# esploc.net
KiCad netlist of a schematic drawn in EAGLE
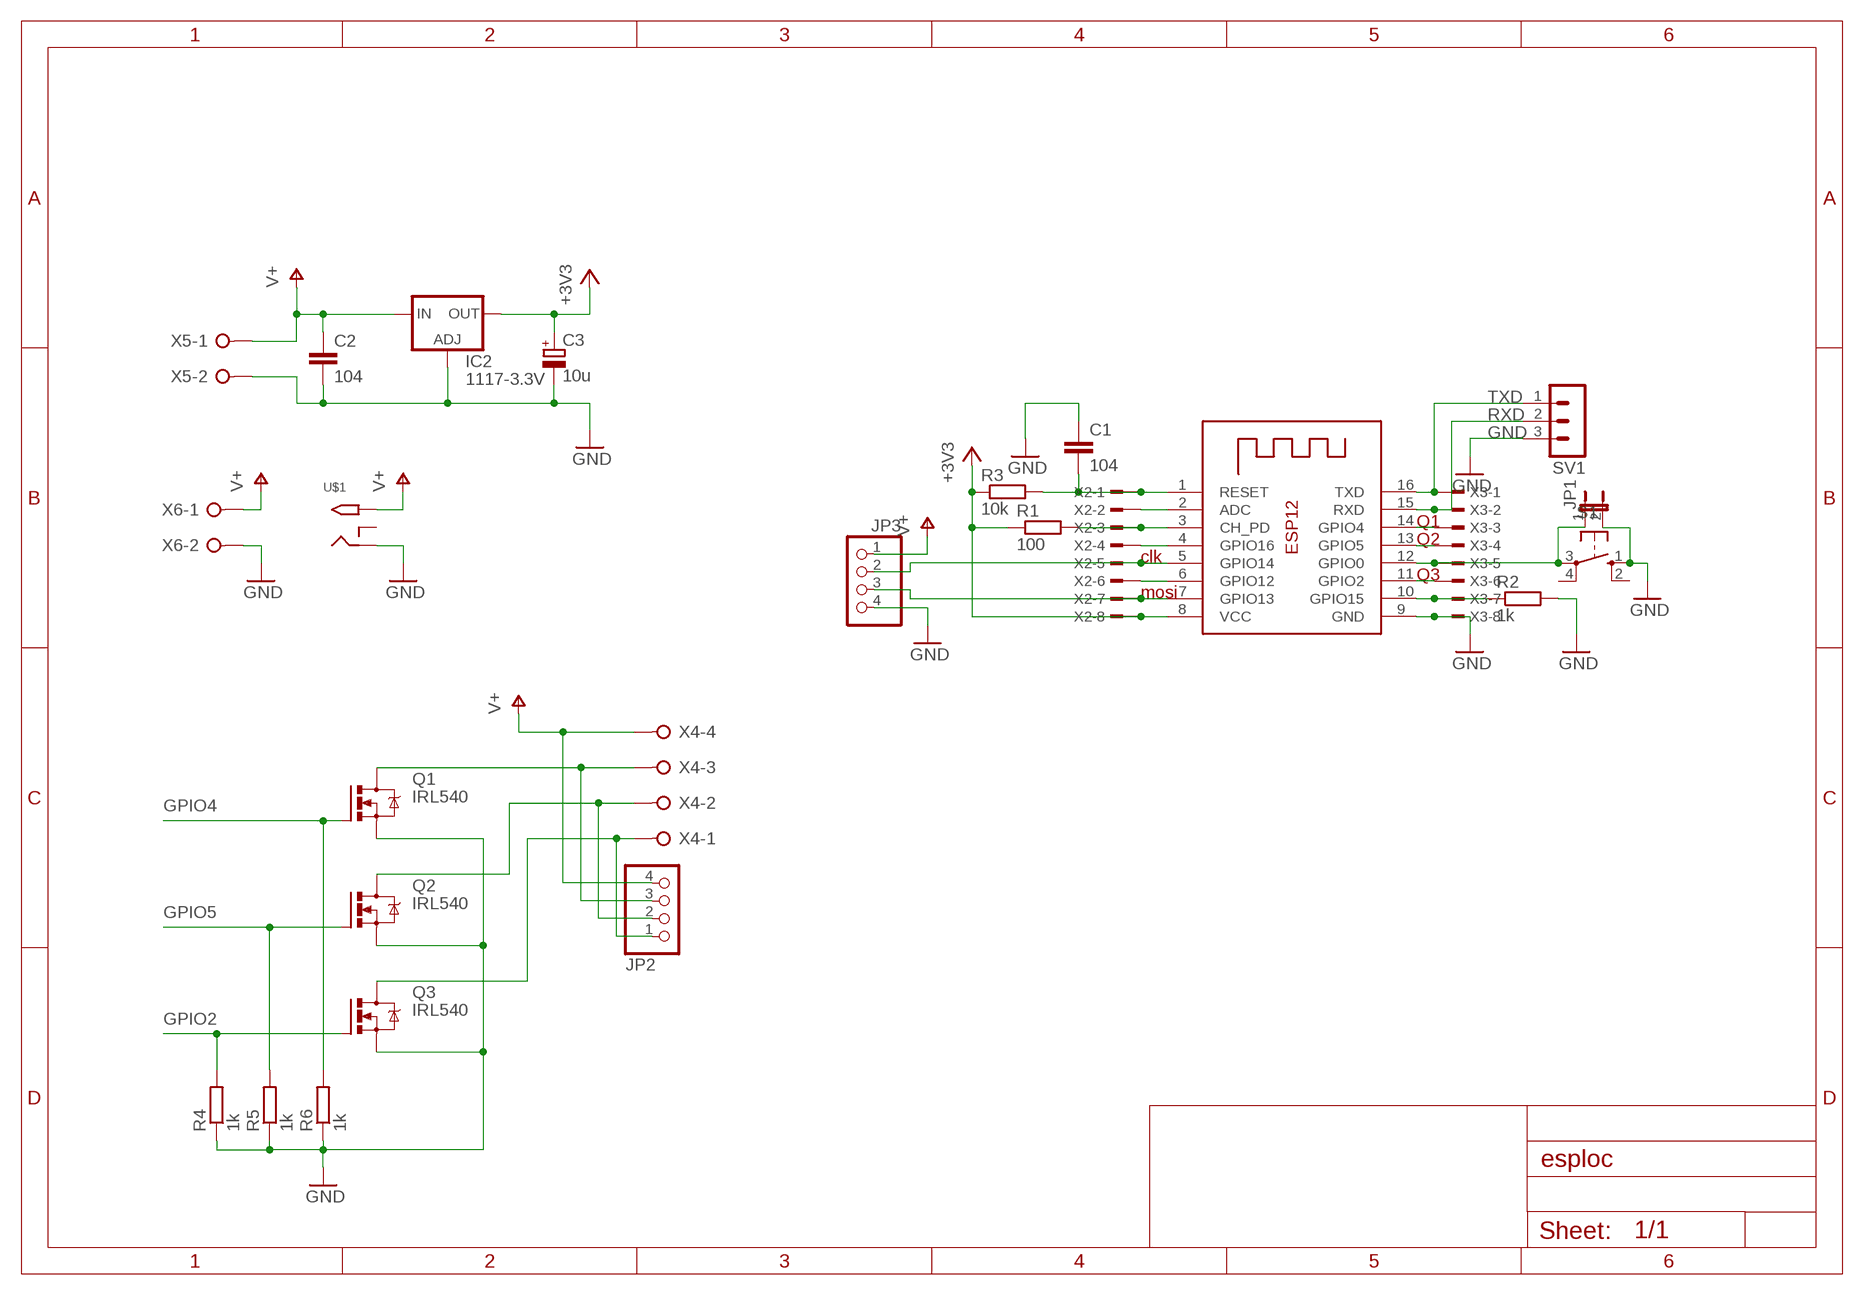
[diagram p0: schematic, sheet 1]

(export (version "E")
  (design (tool "Eeschema 10.0.6"))
  (components
    (comp (ref "C1")
      (value "104")
      (footprint "eagle-import:C025_050-025X075")
      (libsource (lib "eagle-import") (part "C-EU025_050-025X075"))
    )
    (comp (ref "C2")
      (value "104")
      (footprint "eagle-import:C025_050-025X075")
      (libsource (lib "eagle-import") (part "C-EU025_050-025X075"))
    )
    (comp (ref "C3")
      (value "10u")
      (footprint "eagle-import:E2,5-6E")
      (libsource (lib "eagle-import") (part "CPOL-EUE2,5-6E"))
    )
    (comp (ref "IC2")
      (value "1117-3.3V")
      (footprint "eagle-import:SOT223")
      (libsource (lib "eagle-import") (part "LD117A?S33TR"))
    )
    (comp (ref "JP1")
      (value "JP1E")
      (footprint "eagle-import:JP1")
      (libsource (lib "eagle-import") (part "JP1E"))
    )
    (comp (ref "JP2")
      (value "PINHD-1X4")
      (footprint "eagle-import:1X04")
      (libsource (lib "eagle-import") (part "PINHD-1X4"))
    )
    (comp (ref "JP3")
      (value "PINHD-1X4")
      (footprint "eagle-import:1X04")
      (libsource (lib "eagle-import") (part "PINHD-1X4"))
    )
    (comp (ref "Q1")
      (value "IRL540")
      (footprint "eagle-import:TO220BV")
      (libsource (lib "eagle-import") (part "IRF540"))
    )
    (comp (ref "Q2")
      (value "IRL540")
      (footprint "eagle-import:TO220BV")
      (libsource (lib "eagle-import") (part "IRF540"))
    )
    (comp (ref "Q3")
      (value "IRL540")
      (footprint "eagle-import:TO220BV")
      (libsource (lib "eagle-import") (part "IRF540"))
    )
    (comp (ref "R1")
      (value "100")
      (footprint "eagle-import:M0805")
      (libsource (lib "eagle-import") (part "R-EU_M0805"))
    )
    (comp (ref "R2")
      (value "1k")
      (footprint "eagle-import:M0805")
      (libsource (lib "eagle-import") (part "R-EU_M0805"))
    )
    (comp (ref "R3")
      (value "10k")
      (footprint "eagle-import:M0805")
      (libsource (lib "eagle-import") (part "R-EU_M0805"))
    )
    (comp (ref "R4")
      (value "1k")
      (footprint "eagle-import:M0805")
      (libsource (lib "eagle-import") (part "R-EU_M0805"))
    )
    (comp (ref "R5")
      (value "1k")
      (footprint "eagle-import:M0805")
      (libsource (lib "eagle-import") (part "R-EU_M0805"))
    )
    (comp (ref "R6")
      (value "1k")
      (footprint "eagle-import:M0805")
      (libsource (lib "eagle-import") (part "R-EU_M0805"))
    )
    (comp (ref "S1")
      (value "40-XX")
      (footprint "eagle-import:B3F-40XX")
      (fields (field (name "MF") "OMRON COMPONENTS USA") (field (name "MPN") "B3F-4000"))
      (libsource (lib "eagle-import") (part "40-XX"))
    )
    (comp (ref "SV1")
      (value "MA03-1")
      (footprint "eagle-import:MA03-1")
      (libsource (lib "eagle-import") (part "MA03-1"))
    )
    (comp (ref "U$1")
      (value "2.1MMJACKTHM")
      (footprint "eagle-import:PJ-102A")
      (libsource (lib "eagle-import") (part "2.1MMJACKTHM"))
    )
    (comp (ref "X1")
      (value "ESP-12")
      (footprint "eagle-import:ESP-12")
      (libsource (lib "eagle-import") (part "ESP-12"))
    )
    (comp (ref "X2")
      (value "TSW-108-02-S-S")
      (footprint "eagle-import:TSW-108-02-S-S")
      (libsource (lib "eagle-import") (part "TSW-108-02-S-S"))
    )
    (comp (ref "X3")
      (value "TSW-108-02-S-S")
      (footprint "eagle-import:TSW-108-02-S-S")
      (libsource (lib "eagle-import") (part "TSW-108-02-S-S"))
    )
    (comp (ref "X4")
      (value "W237-04P")
      (footprint "eagle-import:W237-4P")
      (libsource (lib "eagle-import") (part "W237-04P"))
    )
    (comp (ref "X5")
      (value "W237-02P")
      (footprint "eagle-import:W237-132")
      (libsource (lib "eagle-import") (part "W237-02P"))
    )
    (comp (ref "X6")
      (value "W237-02P")
      (footprint "eagle-import:W237-132")
      (libsource (lib "eagle-import") (part "W237-02P"))
    )
  )
  (nets
    (net (code "1") (name "+3V3") (class "Default")
      (node (ref "C3") (pin "+") (pinfunction "+_+") (pintype "passive"))
      (node (ref "IC2") (pin "2") (pinfunction "OUT_2") (pintype "passive"))
      (node (ref "IC2") (pin "4") (pinfunction "OUT_4") (pintype "passive"))
      (node (ref "R1") (pin "1") (pinfunction "1_1") (pintype "passive"))
      (node (ref "R3") (pin "1") (pinfunction "1_1") (pintype "passive"))
      (node (ref "X1") (pin "8") (pinfunction "VCC_8") (pintype "power_in"))
      (node (ref "X2") (pin "8") (pinfunction "1_8") (pintype "passive"))
    )
    (net (code "2") (name "/GPIO2") (class "Default")
      (node (ref "Q3") (pin "G") (pinfunction "G_G") (pintype "passive"))
      (node (ref "R4") (pin "2") (pinfunction "2_2") (pintype "passive"))
      (node (ref "X1") (pin "11") (pinfunction "GPIO2_11") (pintype "bidirectional"))
      (node (ref "X3") (pin "6") (pinfunction "1_6") (pintype "passive"))
    )
    (net (code "3") (name "/GPIO4") (class "Default")
      (node (ref "Q1") (pin "G") (pinfunction "G_G") (pintype "passive"))
      (node (ref "R6") (pin "2") (pinfunction "2_2") (pintype "passive"))
      (node (ref "X1") (pin "14") (pinfunction "GPIO4_14") (pintype "bidirectional"))
      (node (ref "X3") (pin "3") (pinfunction "1_3") (pintype "passive"))
    )
    (net (code "4") (name "/GPIO5") (class "Default")
      (node (ref "Q2") (pin "G") (pinfunction "G_G") (pintype "passive"))
      (node (ref "R5") (pin "2") (pinfunction "2_2") (pintype "passive"))
      (node (ref "X1") (pin "13") (pinfunction "GPIO5_13") (pintype "bidirectional"))
      (node (ref "X3") (pin "4") (pinfunction "1_4") (pintype "passive"))
    )
    (net (code "5") (name "/RXD") (class "Default")
      (node (ref "SV1") (pin "2") (pinfunction "2_2") (pintype "passive"))
      (node (ref "X1") (pin "15") (pinfunction "RXD_15") (pintype "input"))
      (node (ref "X3") (pin "2") (pinfunction "1_2") (pintype "passive"))
    )
    (net (code "6") (name "/TXD") (class "Default")
      (node (ref "SV1") (pin "1") (pinfunction "1_1") (pintype "passive"))
      (node (ref "X1") (pin "16") (pinfunction "TXD_16") (pintype "output"))
      (node (ref "X3") (pin "1") (pinfunction "1_1") (pintype "passive"))
    )
    (net (code "7") (name "GND") (class "Default")
      (node (ref "C1") (pin "1") (pinfunction "1_1") (pintype "passive"))
      (node (ref "C2") (pin "2") (pinfunction "2_2") (pintype "passive"))
      (node (ref "C3") (pin "-") (pinfunction "-_-") (pintype "passive"))
      (node (ref "IC2") (pin "1") (pinfunction "ADJ_1") (pintype "input"))
      (node (ref "JP1") (pin "2") (pinfunction "2_2") (pintype "passive"))
      (node (ref "JP3") (pin "4") (pinfunction "4_4") (pintype "passive"))
      (node (ref "Q1") (pin "S") (pinfunction "S_S") (pintype "passive"))
      (node (ref "Q2") (pin "S") (pinfunction "S_S") (pintype "passive"))
      (node (ref "Q3") (pin "S") (pinfunction "S_S") (pintype "passive"))
      (node (ref "R2") (pin "2") (pinfunction "2_2") (pintype "passive"))
      (node (ref "R4") (pin "1") (pinfunction "1_1") (pintype "passive"))
      (node (ref "R5") (pin "1") (pinfunction "1_1") (pintype "passive"))
      (node (ref "R6") (pin "1") (pinfunction "1_1") (pintype "passive"))
      (node (ref "S1") (pin "1") (pinfunction "S_1") (pintype "passive"))
      (node (ref "SV1") (pin "3") (pinfunction "3_3") (pintype "passive"))
      (node (ref "U$1") (pin "RING") (pinfunction "RING_RING") (pintype "bidirectional"))
      (node (ref "X1") (pin "9") (pinfunction "GND_9") (pintype "power_in"))
      (node (ref "X3") (pin "8") (pinfunction "1_8") (pintype "passive"))
      (node (ref "X5") (pin "2") (pinfunction "KL_2") (pintype "passive"))
      (node (ref "X6") (pin "2") (pinfunction "KL_2") (pintype "passive"))
    )
    (net (code "8") (name "Net-(S1-P)") (class "Default")
      (node (ref "JP1") (pin "1") (pinfunction "1_1") (pintype "passive"))
      (node (ref "S1") (pin "3") (pinfunction "P_3") (pintype "passive"))
      (node (ref "X1") (pin "12") (pinfunction "GPIO0_12") (pintype "bidirectional"))
      (node (ref "X3") (pin "5") (pinfunction "1_5") (pintype "passive"))
    )
    (net (code "9") (name "Net-(X1-ADC)") (class "Default")
      (node (ref "X1") (pin "2") (pinfunction "ADC_2") (pintype "passive"))
      (node (ref "X2") (pin "2") (pinfunction "1_2") (pintype "passive"))
    )
    (net (code "10") (name "Net-(X1-CH_PD)") (class "Default")
      (node (ref "R1") (pin "2") (pinfunction "2_2") (pintype "passive"))
      (node (ref "X1") (pin "3") (pinfunction "CH_PD_3") (pintype "input"))
      (node (ref "X2") (pin "3") (pinfunction "1_3") (pintype "passive"))
    )
    (net (code "11") (name "Net-(X1-GPIO12)") (class "Default")
      (node (ref "X1") (pin "6") (pinfunction "GPIO12_6") (pintype "bidirectional"))
      (node (ref "X2") (pin "6") (pinfunction "1_6") (pintype "passive"))
    )
    (net (code "12") (name "Net-(X1-GPIO13)") (class "Default")
      (node (ref "JP3") (pin "3") (pinfunction "3_3") (pintype "passive"))
      (node (ref "X1") (pin "7") (pinfunction "GPIO13_7") (pintype "bidirectional"))
      (node (ref "X2") (pin "7") (pinfunction "1_7") (pintype "passive"))
    )
    (net (code "13") (name "Net-(X1-GPIO14)") (class "Default")
      (node (ref "JP3") (pin "2") (pinfunction "2_2") (pintype "passive"))
      (node (ref "X1") (pin "5") (pinfunction "GPIO14_5") (pintype "bidirectional"))
      (node (ref "X2") (pin "5") (pinfunction "1_5") (pintype "passive"))
    )
    (net (code "14") (name "Net-(X1-GPIO15)") (class "Default")
      (node (ref "R2") (pin "1") (pinfunction "1_1") (pintype "passive"))
      (node (ref "X1") (pin "10") (pinfunction "GPIO15_10") (pintype "bidirectional"))
      (node (ref "X3") (pin "7") (pinfunction "1_7") (pintype "passive"))
    )
    (net (code "15") (name "Net-(X1-GPIO16)") (class "Default")
      (node (ref "X1") (pin "4") (pinfunction "GPIO16_4") (pintype "bidirectional"))
      (node (ref "X2") (pin "4") (pinfunction "1_4") (pintype "passive"))
    )
    (net (code "16") (name "Net-(X1-RESET)") (class "Default")
      (node (ref "C1") (pin "2") (pinfunction "2_2") (pintype "passive"))
      (node (ref "R3") (pin "2") (pinfunction "2_2") (pintype "passive"))
      (node (ref "X1") (pin "1") (pinfunction "RESET_1") (pintype "input"))
      (node (ref "X2") (pin "1") (pinfunction "1_1") (pintype "passive"))
    )
    (net (code "17") (name "Net-(X4A-KL)") (class "Default")
      (node (ref "JP2") (pin "1") (pinfunction "1_1") (pintype "passive"))
      (node (ref "Q3") (pin "D") (pinfunction "D_D") (pintype "passive"))
      (node (ref "X4") (pin "1") (pinfunction "KL_1") (pintype "passive"))
    )
    (net (code "18") (name "Net-(X4B-KL)") (class "Default")
      (node (ref "JP2") (pin "2") (pinfunction "2_2") (pintype "passive"))
      (node (ref "Q2") (pin "D") (pinfunction "D_D") (pintype "passive"))
      (node (ref "X4") (pin "2") (pinfunction "KL_2") (pintype "passive"))
    )
    (net (code "19") (name "Net-(X4C-KL)") (class "Default")
      (node (ref "JP2") (pin "3") (pinfunction "3_3") (pintype "passive"))
      (node (ref "Q1") (pin "D") (pinfunction "D_D") (pintype "passive"))
      (node (ref "X4") (pin "3") (pinfunction "KL_3") (pintype "passive"))
    )
    (net (code "20") (name "V+") (class "Default")
      (node (ref "C2") (pin "1") (pinfunction "1_1") (pintype "passive"))
      (node (ref "IC2") (pin "3") (pinfunction "IN_3") (pintype "input"))
      (node (ref "JP2") (pin "4") (pinfunction "4_4") (pintype "passive"))
      (node (ref "JP3") (pin "1") (pinfunction "1_1") (pintype "passive"))
      (node (ref "U$1") (pin "TIP") (pinfunction "TIP_TIP") (pintype "bidirectional"))
      (node (ref "X4") (pin "4") (pinfunction "KL_4") (pintype "passive"))
      (node (ref "X5") (pin "1") (pinfunction "KL_1") (pintype "passive"))
      (node (ref "X6") (pin "1") (pinfunction "KL_1") (pintype "passive"))
    )
    (net (code "21") (name "unconnected-(S1-P1-Pad4)") (class "Default")
      (node (ref "S1") (pin "4") (pinfunction "P1_4") (pintype "passive"))
    )
    (net (code "22") (name "unconnected-(S1-S1-Pad2)") (class "Default")
      (node (ref "S1") (pin "2") (pinfunction "S1_2") (pintype "passive"))
    )
    (net (code "23") (name "unconnected-(U$1-PadRING_SW)") (class "Default")
      (node (ref "U$1") (pin "RING_SW") (pinfunction "RING_SW_RING_SW") (pintype "bidirectional"))
    )
  )
)
